# notre_carte.net
KiCad netlist of a schematic drawn in EAGLE
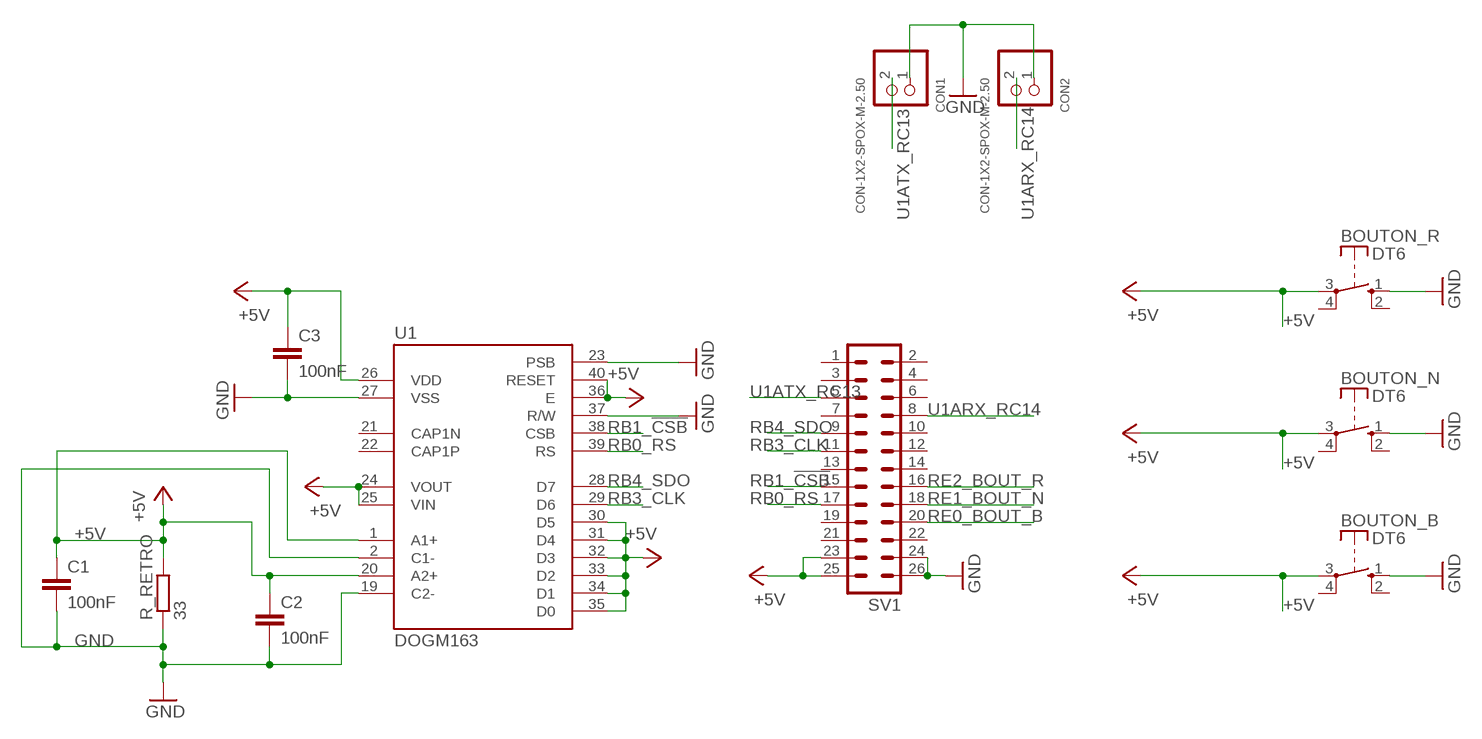
[diagram p0: schematic, sheet 1]

(export (version "E")
  (design (tool "Eeschema 10.0.6"))
  (components
    (comp (ref "BOUTON_B")
      (value "DT6")
      (footprint "eagle-import:DT6")
      (libsource (lib "eagle-import") (part "DT6"))
    )
    (comp (ref "BOUTON_N")
      (value "DT6")
      (footprint "eagle-import:DT6")
      (libsource (lib "eagle-import") (part "DT6"))
    )
    (comp (ref "BOUTON_R")
      (value "DT6")
      (footprint "eagle-import:DT6")
      (libsource (lib "eagle-import") (part "DT6"))
    )
    (comp (ref "C1")
      (value "100nF")
      (footprint "eagle-import:C025-025X050")
      (libsource (lib "eagle-import") (part "C-EU025-025X050"))
    )
    (comp (ref "C2")
      (value "100nF")
      (footprint "eagle-import:C025-025X050")
      (libsource (lib "eagle-import") (part "C-EU025-025X050"))
    )
    (comp (ref "C3")
      (value "100nF")
      (footprint "eagle-import:C025-025X050")
      (libsource (lib "eagle-import") (part "C-EU025-025X050"))
    )
    (comp (ref "CON1")
      (value "CON-1X2-SPOX-M-2.50")
      (footprint "eagle-import:SPOX-M-2.50-02")
      (libsource (lib "eagle-import") (part "CON-1X2-SPOX-M-2.50"))
    )
    (comp (ref "CON2")
      (value "CON-1X2-SPOX-M-2.50")
      (footprint "eagle-import:SPOX-M-2.50-02")
      (libsource (lib "eagle-import") (part "CON-1X2-SPOX-M-2.50"))
    )
    (comp (ref "R_RETRO")
      (value "33")
      (footprint "eagle-import:0207_15")
      (libsource (lib "eagle-import") (part "R-EU_0207/15"))
    )
    (comp (ref "SV1")
      (value "ML26")
      (footprint "eagle-import:ML26")
      (libsource (lib "eagle-import") (part "ML26"))
    )
    (comp (ref "U1")
      (value "DOGM163")
      (footprint "eagle-import:DOGM")
      (libsource (lib "eagle-import") (part "DOGM163"))
    )
  )
  (nets
    (net (code "1") (name "+5V") (class "Default")
      (node (ref "BOUTON_B") (pin "3") (pinfunction "P_3") (pintype "passive"))
      (node (ref "BOUTON_N") (pin "3") (pinfunction "P_3") (pintype "passive"))
      (node (ref "BOUTON_R") (pin "3") (pinfunction "P_3") (pintype "passive"))
      (node (ref "C1") (pin "1") (pinfunction "1_1") (pintype "passive"))
      (node (ref "C2") (pin "1") (pinfunction "1_1") (pintype "passive"))
      (node (ref "C3") (pin "1") (pinfunction "1_1") (pintype "passive"))
      (node (ref "R_RETRO") (pin "2") (pinfunction "2_2") (pintype "passive"))
      (node (ref "SV1") (pin "23") (pinfunction "23_23") (pintype "passive"))
      (node (ref "SV1") (pin "25") (pinfunction "25_25") (pintype "passive"))
      (node (ref "U1") (pin "1") (pinfunction "A1+_1") (pintype "bidirectional"))
      (node (ref "U1") (pin "20") (pinfunction "A2+_20") (pintype "bidirectional"))
      (node (ref "U1") (pin "24") (pinfunction "VOUT_24") (pintype "bidirectional"))
      (node (ref "U1") (pin "25") (pinfunction "VIN_25") (pintype "bidirectional"))
      (node (ref "U1") (pin "26") (pinfunction "VDD_26") (pintype "bidirectional"))
      (node (ref "U1") (pin "30") (pinfunction "D5_30") (pintype "bidirectional"))
      (node (ref "U1") (pin "31") (pinfunction "D4_31") (pintype "bidirectional"))
      (node (ref "U1") (pin "32") (pinfunction "D3_32") (pintype "bidirectional"))
      (node (ref "U1") (pin "33") (pinfunction "D2_33") (pintype "bidirectional"))
      (node (ref "U1") (pin "34") (pinfunction "D1_34") (pintype "bidirectional"))
      (node (ref "U1") (pin "35") (pinfunction "D0_35") (pintype "bidirectional"))
      (node (ref "U1") (pin "36") (pinfunction "E_36") (pintype "bidirectional"))
      (node (ref "U1") (pin "40") (pinfunction "RESET_40") (pintype "bidirectional"))
    )
    (net (code "2") (name "/RB0_RS") (class "Default")
      (node (ref "SV1") (pin "17") (pinfunction "17_17") (pintype "passive"))
      (node (ref "U1") (pin "39") (pinfunction "RS_39") (pintype "bidirectional"))
    )
    (net (code "3") (name "/RB1_~{CSB}") (class "Default")
      (node (ref "SV1") (pin "15") (pinfunction "15_15") (pintype "passive"))
      (node (ref "U1") (pin "38") (pinfunction "CSB_38") (pintype "bidirectional"))
    )
    (net (code "4") (name "/RB3_CLK") (class "Default")
      (node (ref "SV1") (pin "11") (pinfunction "11_11") (pintype "passive"))
      (node (ref "U1") (pin "29") (pinfunction "D6_29") (pintype "bidirectional"))
    )
    (net (code "5") (name "/RB4_SDO") (class "Default")
      (node (ref "SV1") (pin "9") (pinfunction "9_9") (pintype "passive"))
      (node (ref "U1") (pin "28") (pinfunction "D7_28") (pintype "bidirectional"))
    )
    (net (code "6") (name "/RE0_BOUT_B") (class "Default")
      (node (ref "SV1") (pin "20") (pinfunction "20_20") (pintype "passive"))
    )
    (net (code "7") (name "/RE1_BOUT_N") (class "Default")
      (node (ref "SV1") (pin "18") (pinfunction "18_18") (pintype "passive"))
    )
    (net (code "8") (name "/RE2_BOUT_R") (class "Default")
      (node (ref "SV1") (pin "16") (pinfunction "16_16") (pintype "passive"))
    )
    (net (code "9") (name "/U1ARX_RC14") (class "Default")
      (node (ref "CON2") (pin "2") (pinfunction "2_2") (pintype "passive"))
      (node (ref "SV1") (pin "8") (pinfunction "8_8") (pintype "passive"))
    )
    (net (code "10") (name "/U1ATX_RC13") (class "Default")
      (node (ref "CON1") (pin "2") (pinfunction "2_2") (pintype "passive"))
      (node (ref "SV1") (pin "5") (pinfunction "5_5") (pintype "passive"))
    )
    (net (code "11") (name "GND") (class "Default")
      (node (ref "BOUTON_B") (pin "1") (pinfunction "S_1") (pintype "passive"))
      (node (ref "BOUTON_N") (pin "1") (pinfunction "S_1") (pintype "passive"))
      (node (ref "BOUTON_R") (pin "1") (pinfunction "S_1") (pintype "passive"))
      (node (ref "C1") (pin "2") (pinfunction "2_2") (pintype "passive"))
      (node (ref "C2") (pin "2") (pinfunction "2_2") (pintype "passive"))
      (node (ref "C3") (pin "2") (pinfunction "2_2") (pintype "passive"))
      (node (ref "CON1") (pin "1") (pinfunction "1_1") (pintype "passive"))
      (node (ref "CON2") (pin "1") (pinfunction "1_1") (pintype "passive"))
      (node (ref "R_RETRO") (pin "1") (pinfunction "1_1") (pintype "passive"))
      (node (ref "SV1") (pin "24") (pinfunction "24_24") (pintype "passive"))
      (node (ref "SV1") (pin "26") (pinfunction "26_26") (pintype "passive"))
      (node (ref "U1") (pin "19") (pinfunction "C2-_19") (pintype "bidirectional"))
      (node (ref "U1") (pin "2") (pinfunction "C1-_2") (pintype "bidirectional"))
      (node (ref "U1") (pin "23") (pinfunction "PSB_23") (pintype "bidirectional"))
      (node (ref "U1") (pin "27") (pinfunction "VSS_27") (pintype "bidirectional"))
      (node (ref "U1") (pin "37") (pinfunction "R/W_37") (pintype "bidirectional"))
    )
    (net (code "12") (name "unconnected-(BOUTON_B-P-Pad4)") (class "Default")
      (node (ref "BOUTON_B") (pin "4") (pinfunction "P_4") (pintype "passive"))
    )
    (net (code "13") (name "unconnected-(BOUTON_B-S-Pad2)") (class "Default")
      (node (ref "BOUTON_B") (pin "2") (pinfunction "S_2") (pintype "passive"))
    )
    (net (code "14") (name "unconnected-(BOUTON_N-P-Pad4)") (class "Default")
      (node (ref "BOUTON_N") (pin "4") (pinfunction "P_4") (pintype "passive"))
    )
    (net (code "15") (name "unconnected-(BOUTON_N-S-Pad2)") (class "Default")
      (node (ref "BOUTON_N") (pin "2") (pinfunction "S_2") (pintype "passive"))
    )
    (net (code "16") (name "unconnected-(BOUTON_R-P-Pad4)") (class "Default")
      (node (ref "BOUTON_R") (pin "4") (pinfunction "P_4") (pintype "passive"))
    )
    (net (code "17") (name "unconnected-(BOUTON_R-S-Pad2)") (class "Default")
      (node (ref "BOUTON_R") (pin "2") (pinfunction "S_2") (pintype "passive"))
    )
    (net (code "18") (name "unconnected-(SV1-Pad1)") (class "Default")
      (node (ref "SV1") (pin "1") (pinfunction "1_1") (pintype "passive"))
    )
    (net (code "19") (name "unconnected-(SV1-Pad2)") (class "Default")
      (node (ref "SV1") (pin "2") (pinfunction "2_2") (pintype "passive"))
    )
    (net (code "20") (name "unconnected-(SV1-Pad3)") (class "Default")
      (node (ref "SV1") (pin "3") (pinfunction "3_3") (pintype "passive"))
    )
    (net (code "21") (name "unconnected-(SV1-Pad4)") (class "Default")
      (node (ref "SV1") (pin "4") (pinfunction "4_4") (pintype "passive"))
    )
    (net (code "22") (name "unconnected-(SV1-Pad6)") (class "Default")
      (node (ref "SV1") (pin "6") (pinfunction "6_6") (pintype "passive"))
    )
    (net (code "23") (name "unconnected-(SV1-Pad7)") (class "Default")
      (node (ref "SV1") (pin "7") (pinfunction "7_7") (pintype "passive"))
    )
    (net (code "24") (name "unconnected-(SV1-Pad10)") (class "Default")
      (node (ref "SV1") (pin "10") (pinfunction "10_10") (pintype "passive"))
    )
    (net (code "25") (name "unconnected-(SV1-Pad12)") (class "Default")
      (node (ref "SV1") (pin "12") (pinfunction "12_12") (pintype "passive"))
    )
    (net (code "26") (name "unconnected-(SV1-Pad13)") (class "Default")
      (node (ref "SV1") (pin "13") (pinfunction "13_13") (pintype "passive"))
    )
    (net (code "27") (name "unconnected-(SV1-Pad14)") (class "Default")
      (node (ref "SV1") (pin "14") (pinfunction "14_14") (pintype "passive"))
    )
    (net (code "28") (name "unconnected-(SV1-Pad19)") (class "Default")
      (node (ref "SV1") (pin "19") (pinfunction "19_19") (pintype "passive"))
    )
    (net (code "29") (name "unconnected-(SV1-Pad21)") (class "Default")
      (node (ref "SV1") (pin "21") (pinfunction "21_21") (pintype "passive"))
    )
    (net (code "30") (name "unconnected-(SV1-Pad22)") (class "Default")
      (node (ref "SV1") (pin "22") (pinfunction "22_22") (pintype "passive"))
    )
    (net (code "31") (name "unconnected-(U1-CAP1N-Pad21)") (class "Default")
      (node (ref "U1") (pin "21") (pinfunction "CAP1N_21") (pintype "bidirectional"))
    )
    (net (code "32") (name "unconnected-(U1-CAP1P-Pad22)") (class "Default")
      (node (ref "U1") (pin "22") (pinfunction "CAP1P_22") (pintype "bidirectional"))
    )
  )
)
